# schematic-easyeda.net
KiCad netlist of a schematic drawn in EasyEDA
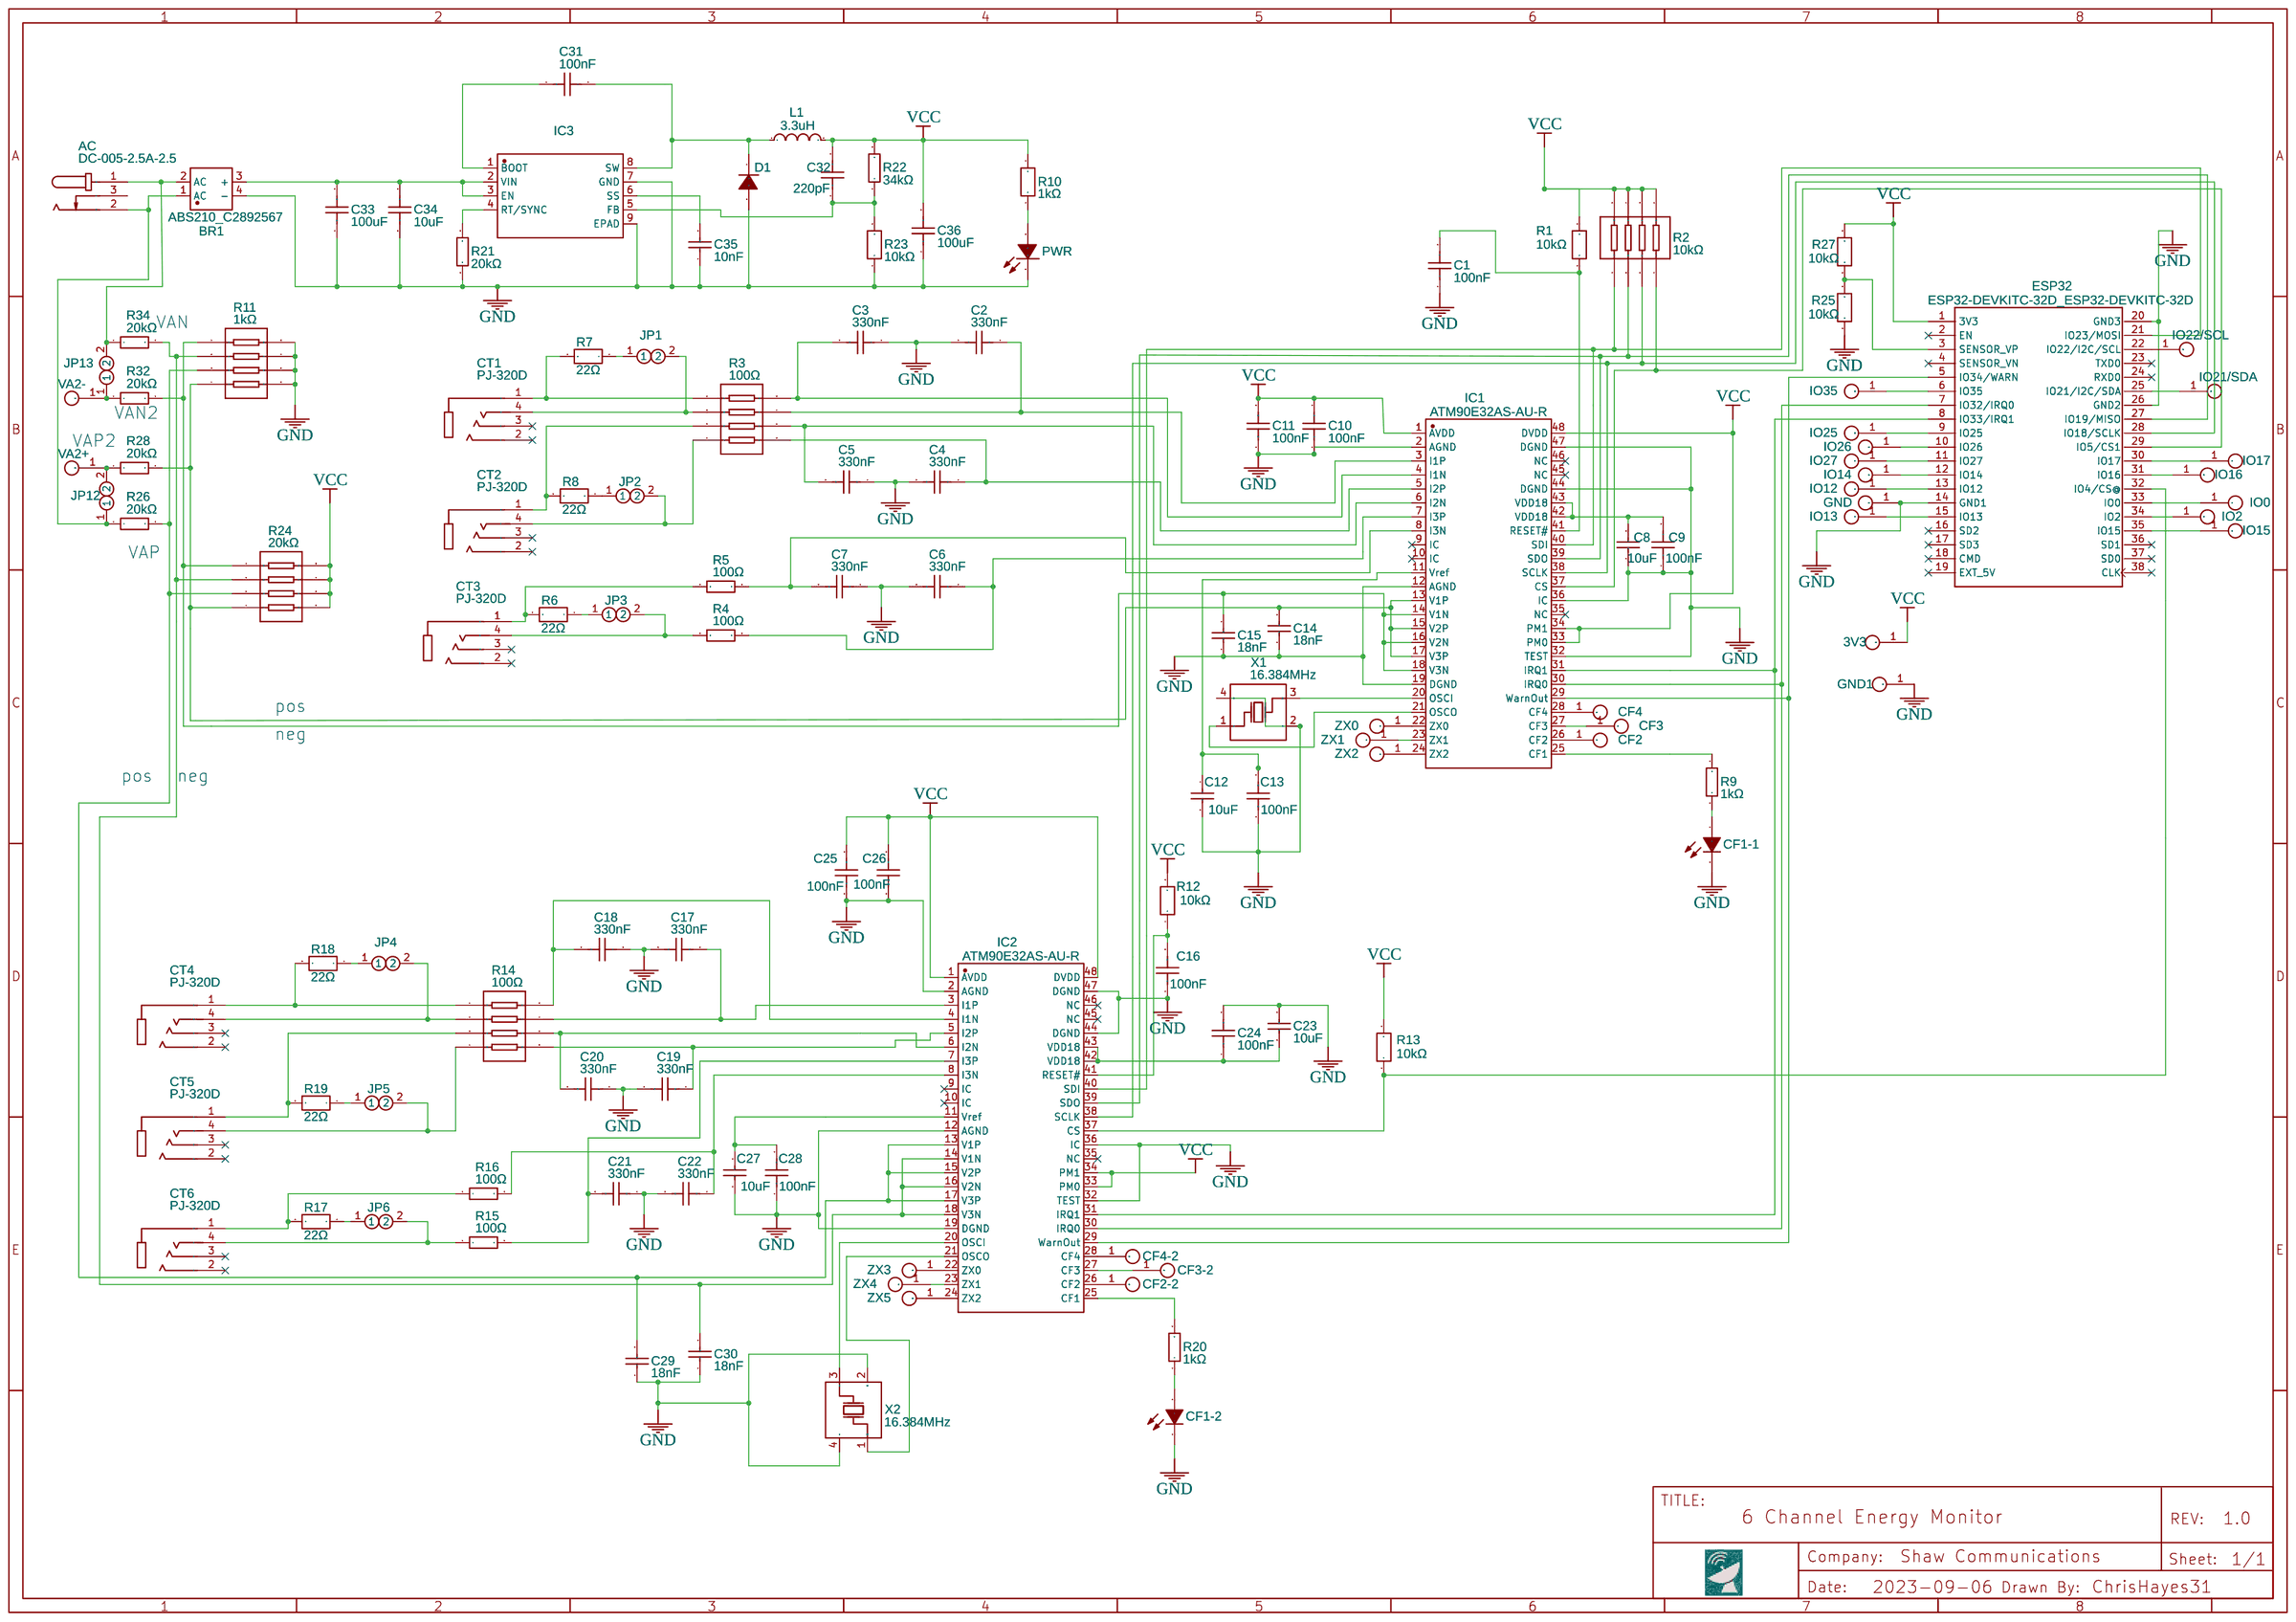
[diagram p0: schematic sheet]

(export (version "E")
  (design (tool "Eeschema 10.0.6"))
  (components
    (comp (ref "3V3") (value "PAD-ROUND") (libsource (lib "") (part "PAD-ROUND_5")))
    (comp (ref "AC")
      (value "DC-005-2.5A-2.5")
      (fields (field (name "Manufacturer") "XKB Enterprise"))
      (libsource (lib "") (part "DC-005-2.5A-2.5"))
    )
    (comp (ref "BR1")
      (value "ABS210_C2892567")
      (fields (field (name "Manufacturer Part") "ABS210") (field (name "Manufacturer") "YONGYUTAI(永裕泰)"))
      (libsource (lib "") (part "ABS210_C2892567"))
    )
    (comp (ref "C1")
      (value "100nF")
      (fields (field (name "Manufacturer Part") "CGJ4J2X7R1E104K125AA") (field (name "Manufacturer") "TDK"))
      (libsource (lib "") (part "CGJ4J2X7R1E104K125AA"))
    )
    (comp (ref "C2")
      (value "330nF")
      (fields
        (field (name "Manufacturer Part") "TCC0805X7R334K500DT")
        (field (name "Manufacturer") "CCTC(三环)")
      )
      (libsource (lib "") (part "TCC0805X7R334K500DT"))
    )
    (comp (ref "C3")
      (value "330nF")
      (fields
        (field (name "Manufacturer Part") "TCC0805X7R334K500DT")
        (field (name "Manufacturer") "CCTC(三环)")
      )
      (libsource (lib "") (part "TCC0805X7R334K500DT"))
    )
    (comp (ref "C4")
      (value "330nF")
      (fields
        (field (name "Manufacturer Part") "TCC0805X7R334K500DT")
        (field (name "Manufacturer") "CCTC(三环)")
      )
      (libsource (lib "") (part "TCC0805X7R334K500DT"))
    )
    (comp (ref "C5")
      (value "330nF")
      (fields
        (field (name "Manufacturer Part") "TCC0805X7R334K500DT")
        (field (name "Manufacturer") "CCTC(三环)")
      )
      (libsource (lib "") (part "TCC0805X7R334K500DT"))
    )
    (comp (ref "C6")
      (value "330nF")
      (fields
        (field (name "Manufacturer Part") "TCC0805X7R334K500DT")
        (field (name "Manufacturer") "CCTC(三环)")
      )
      (libsource (lib "") (part "TCC0805X7R334K500DT"))
    )
    (comp (ref "C7")
      (value "330nF")
      (fields
        (field (name "Manufacturer Part") "TCC0805X7R334K500DT")
        (field (name "Manufacturer") "CCTC(三环)")
      )
      (libsource (lib "") (part "TCC0805X7R334K500DT"))
    )
    (comp (ref "C8")
      (value "10uF")
      (fields
        (field (name "Manufacturer Part") "CC0805KKX5R8BB106")
        (field (name "Manufacturer") "YAGEO(国巨)")
      )
      (libsource (lib "") (part "CC0805KKX5R8BB106"))
    )
    (comp (ref "C9")
      (value "100nF")
      (fields (field (name "Manufacturer Part") "CGJ4J2X7R1E104K125AA") (field (name "Manufacturer") "TDK"))
      (libsource (lib "") (part "CGJ4J2X7R1E104K125AA"))
    )
    (comp (ref "C10")
      (value "100nF")
      (fields (field (name "Manufacturer Part") "CGJ4J2X7R1E104K125AA") (field (name "Manufacturer") "TDK"))
      (libsource (lib "") (part "CGJ4J2X7R1E104K125AA"))
    )
    (comp (ref "C11")
      (value "100nF")
      (fields (field (name "Manufacturer Part") "CGJ4J2X7R1E104K125AA") (field (name "Manufacturer") "TDK"))
      (libsource (lib "") (part "CGJ4J2X7R1E104K125AA"))
    )
    (comp (ref "C12")
      (value "10uF")
      (fields
        (field (name "Manufacturer Part") "CC0805KKX5R8BB106")
        (field (name "Manufacturer") "YAGEO(国巨)")
      )
      (libsource (lib "") (part "CC0805KKX5R8BB106_1"))
    )
    (comp (ref "C13")
      (value "100nF")
      (fields (field (name "Manufacturer Part") "CGJ4J2X7R1E104K125AA") (field (name "Manufacturer") "TDK"))
      (libsource (lib "") (part "CGJ4J2X7R1E104K125AA"))
    )
    (comp (ref "C14")
      (value "18nF")
      (fields
        (field (name "Manufacturer Part") "CC0805KRX7R9BB183")
        (field (name "Manufacturer") "YAGEO(国巨)")
      )
      (libsource (lib "") (part "CC0805KRX7R9BB183"))
    )
    (comp (ref "C15")
      (value "18nF")
      (fields
        (field (name "Manufacturer Part") "CC0805KRX7R9BB183")
        (field (name "Manufacturer") "YAGEO(国巨)")
      )
      (libsource (lib "") (part "CC0805KRX7R9BB183"))
    )
    (comp (ref "C16")
      (value "100nF")
      (fields (field (name "Manufacturer Part") "CGJ4J2X7R1E104K125AA") (field (name "Manufacturer") "TDK"))
      (libsource (lib "") (part "CGJ4J2X7R1E104K125AA"))
    )
    (comp (ref "C17")
      (value "330nF")
      (fields
        (field (name "Manufacturer Part") "TCC0805X7R334K500DT")
        (field (name "Manufacturer") "CCTC(三环)")
      )
      (libsource (lib "") (part "TCC0805X7R334K500DT"))
    )
    (comp (ref "C18")
      (value "330nF")
      (fields
        (field (name "Manufacturer Part") "TCC0805X7R334K500DT")
        (field (name "Manufacturer") "CCTC(三环)")
      )
      (libsource (lib "") (part "TCC0805X7R334K500DT"))
    )
    (comp (ref "C19")
      (value "330nF")
      (fields
        (field (name "Manufacturer Part") "TCC0805X7R334K500DT")
        (field (name "Manufacturer") "CCTC(三环)")
      )
      (libsource (lib "") (part "TCC0805X7R334K500DT"))
    )
    (comp (ref "C20")
      (value "330nF")
      (fields
        (field (name "Manufacturer Part") "TCC0805X7R334K500DT")
        (field (name "Manufacturer") "CCTC(三环)")
      )
      (libsource (lib "") (part "TCC0805X7R334K500DT"))
    )
    (comp (ref "C21")
      (value "330nF")
      (fields
        (field (name "Manufacturer Part") "TCC0805X7R334K500DT")
        (field (name "Manufacturer") "CCTC(三环)")
      )
      (libsource (lib "") (part "TCC0805X7R334K500DT"))
    )
    (comp (ref "C22")
      (value "330nF")
      (fields
        (field (name "Manufacturer Part") "TCC0805X7R334K500DT")
        (field (name "Manufacturer") "CCTC(三环)")
      )
      (libsource (lib "") (part "TCC0805X7R334K500DT"))
    )
    (comp (ref "C23")
      (value "10uF")
      (fields
        (field (name "Manufacturer Part") "CC0805KKX5R8BB106")
        (field (name "Manufacturer") "YAGEO(国巨)")
      )
      (libsource (lib "") (part "CC0805KKX5R8BB106"))
    )
    (comp (ref "C24")
      (value "100nF")
      (fields (field (name "Manufacturer Part") "CGJ4J2X7R1E104K125AA") (field (name "Manufacturer") "TDK"))
      (libsource (lib "") (part "CGJ4J2X7R1E104K125AA"))
    )
    (comp (ref "C25")
      (value "100nF")
      (fields (field (name "Manufacturer Part") "CGJ4J2X7R1E104K125AA") (field (name "Manufacturer") "TDK"))
      (libsource (lib "") (part "CGJ4J2X7R1E104K125AA"))
    )
    (comp (ref "C26")
      (value "100nF")
      (fields (field (name "Manufacturer Part") "CGJ4J2X7R1E104K125AA") (field (name "Manufacturer") "TDK"))
      (libsource (lib "") (part "CGJ4J2X7R1E104K125AA"))
    )
    (comp (ref "C27")
      (value "10uF")
      (fields
        (field (name "Manufacturer Part") "CC0805KKX5R8BB106")
        (field (name "Manufacturer") "YAGEO(国巨)")
      )
      (libsource (lib "") (part "CC0805KKX5R8BB106_1"))
    )
    (comp (ref "C28")
      (value "100nF")
      (fields (field (name "Manufacturer Part") "CGJ4J2X7R1E104K125AA") (field (name "Manufacturer") "TDK"))
      (libsource (lib "") (part "CGJ4J2X7R1E104K125AA"))
    )
    (comp (ref "C29")
      (value "18nF")
      (fields
        (field (name "Manufacturer Part") "CC0805KRX7R9BB183")
        (field (name "Manufacturer") "YAGEO(国巨)")
      )
      (libsource (lib "") (part "CC0805KRX7R9BB183"))
    )
    (comp (ref "C30")
      (value "18nF")
      (fields
        (field (name "Manufacturer Part") "CC0805KRX7R9BB183")
        (field (name "Manufacturer") "YAGEO(国巨)")
      )
      (libsource (lib "") (part "CC0805KRX7R9BB183"))
    )
    (comp (ref "C31")
      (value "100nF")
      (fields
        (field (name "Manufacturer Part") "CC0805JRX7R7BB104")
        (field (name "Manufacturer") "YAGEO(国巨)")
      )
      (libsource (lib "") (part "CC0805JRX7R7BB104"))
    )
    (comp (ref "C32")
      (value "220pF")
      (fields
        (field (name "Manufacturer Part") "CC0805JRNPO0BN221")
        (field (name "Manufacturer") "YAGEO(国巨)")
      )
      (libsource (lib "") (part "CC0805JRNPO0BN221"))
    )
    (comp (ref "C33")
      (value "100uF")
      (fields
        (field (name "Manufacturer Part") "GRM21BC80E107ME15L")
        (field (name "Manufacturer") "muRata(村田)")
      )
      (libsource (lib "") (part "GRM21BC80E107ME15L"))
    )
    (comp (ref "C34")
      (value "10uF")
      (fields
        (field (name "Manufacturer Part") "CC0805KKX7R7BB106")
        (field (name "Manufacturer") "YAGEO(国巨)")
      )
      (libsource (lib "") (part "CC0805KKX7R7BB106"))
    )
    (comp (ref "C35")
      (value "10nF")
      (fields
        (field (name "Manufacturer Part") "CC0805KKX7RBBB103")
        (field (name "Manufacturer") "YAGEO(国巨)")
      )
      (libsource (lib "") (part "CC0805KKX7RBBB103"))
    )
    (comp (ref "C36")
      (value "100uF")
      (fields
        (field (name "Manufacturer Part") "GRM21BC80E107ME15L")
        (field (name "Manufacturer") "muRata(村田)")
      )
      (libsource (lib "") (part "GRM21BC80E107ME15L"))
    )
    (comp (ref "CF1-1")
      (value "FC-DA1608BK-470H10")
      (fields (field (name "Manufacturer Part") "NCD0603B1") (field (name "Manufacturer") "国星光电"))
      (libsource (lib "") (part "FC-DA1608BK-470H10"))
    )
    (comp (ref "CF1-2")
      (value "FC-DA1608BK-470H10")
      (fields (field (name "Manufacturer Part") "NCD0603B1") (field (name "Manufacturer") "国星光电"))
      (libsource (lib "") (part "FC-DA1608BK-470H10"))
    )
    (comp (ref "CF2") (value "PAD-ROUND") (libsource (lib "") (part "PAD-ROUND_10")))
    (comp (ref "CF2-2") (value "PAD-ROUND") (libsource (lib "") (part "PAD-ROUND_2")))
    (comp (ref "CF3") (value "PAD-ROUND") (libsource (lib "") (part "PAD-ROUND_10")))
    (comp (ref "CF3-2") (value "PAD-ROUND") (libsource (lib "") (part "PAD-ROUND_12")))
    (comp (ref "CF4") (value "PAD-ROUND") (libsource (lib "") (part "PAD-ROUND_10")))
    (comp (ref "CF4-2") (value "PAD-ROUND") (libsource (lib "") (part "PAD-ROUND_9")))
    (comp (ref "CT1")
      (value "PJ-320D")
      (fields (field (name "Manufacturer") "SHOU HAN"))
      (libsource (lib "") (part "PJ-320D"))
    )
    (comp (ref "CT2")
      (value "PJ-320D")
      (fields (field (name "Manufacturer") "SHOU HAN"))
      (libsource (lib "") (part "PJ-320D"))
    )
    (comp (ref "CT3")
      (value "PJ-320D")
      (fields (field (name "Manufacturer") "SHOU HAN"))
      (libsource (lib "") (part "PJ-320D"))
    )
    (comp (ref "CT4")
      (value "PJ-320D")
      (fields (field (name "Manufacturer") "SHOU HAN"))
      (libsource (lib "") (part "PJ-320D"))
    )
    (comp (ref "CT5")
      (value "PJ-320D")
      (fields (field (name "Manufacturer") "SHOU HAN"))
      (libsource (lib "") (part "PJ-320D"))
    )
    (comp (ref "CT6")
      (value "PJ-320D")
      (fields (field (name "Manufacturer") "SHOU HAN"))
      (libsource (lib "") (part "PJ-320D"))
    )
    (comp (ref "D1")
      (value "M7_C95872")
      (fields (field (name "Manufacturer Part") "M7") (field (name "Manufacturer") "MDD"))
      (libsource (lib "") (part "M7_C95872"))
    )
    (comp (ref "ESP32")
      (value "ESP32-DEVKITC-32D_ESP32-DEVKITC-32D")
      (libsource (lib "") (part "ESP32-DEVKITC-32D_ESP32-DEVKITC-32D"))
    )
    (comp (ref "GND") (value "PAD-ROUND") (libsource (lib "") (part "PAD-ROUND_1")))
    (comp (ref "GND1") (value "PAD-ROUND") (libsource (lib "") (part "PAD-ROUND_1")))
    (comp (ref "IC1")
      (value "ATM90E32AS-AU-R")
      (fields (field (name "Manufacturer") "MICROCHIP(美国微芯)"))
      (libsource (lib "") (part "ATM90E32AS-AU-R"))
    )
    (comp (ref "IC2")
      (value "ATM90E32AS-AU-R")
      (fields (field (name "Manufacturer") "MICROCHIP(美国微芯)"))
      (libsource (lib "") (part "ATM90E32AS-AU-R"))
    )
    (comp (ref "IC3")
      (value "LMR14020SDDAR")
      (fields (field (name "Manufacturer") "TI(德州仪器)"))
      (libsource (lib "") (part "LMR14020SDDAR"))
    )
    (comp (ref "IO0") (value "PAD-ROUND") (libsource (lib "") (part "PAD-ROUND_3")))
    (comp (ref "IO2") (value "PAD-ROUND") (libsource (lib "") (part "PAD-ROUND_3")))
    (comp (ref "IO12") (value "PAD-ROUND") (libsource (lib "") (part "PAD-ROUND")))
    (comp (ref "IO13") (value "PAD-ROUND") (libsource (lib "") (part "PAD-ROUND")))
    (comp (ref "IO14") (value "PAD-ROUND") (libsource (lib "") (part "PAD-ROUND")))
    (comp (ref "IO15") (value "PAD-ROUND") (libsource (lib "") (part "PAD-ROUND_3")))
    (comp (ref "IO16") (value "PAD-ROUND") (libsource (lib "") (part "PAD-ROUND_3")))
    (comp (ref "IO17") (value "PAD-ROUND") (libsource (lib "") (part "PAD-ROUND_3")))
    (comp (ref "IO21/SDA") (value "PAD-ROUND") (libsource (lib "") (part "PAD-ROUND_8")))
    (comp (ref "IO22/SCL") (value "PAD-ROUND") (libsource (lib "") (part "PAD-ROUND_6")))
    (comp (ref "IO25") (value "PAD-ROUND") (libsource (lib "") (part "PAD-ROUND")))
    (comp (ref "IO26") (value "PAD-ROUND") (libsource (lib "") (part "PAD-ROUND")))
    (comp (ref "IO27") (value "PAD-ROUND") (libsource (lib "") (part "PAD-ROUND")))
    (comp (ref "IO35") (value "PAD-ROUND") (libsource (lib "") (part "PAD-ROUND")))
    (comp (ref "JP1") (value "J-pad soldering") (libsource (lib "") (part "J-pad soldering")))
    (comp (ref "JP2") (value "J-pad soldering") (libsource (lib "") (part "J-pad soldering")))
    (comp (ref "JP3") (value "J-pad soldering") (libsource (lib "") (part "J-pad soldering")))
    (comp (ref "JP4") (value "J-pad soldering") (libsource (lib "") (part "J-pad soldering")))
    (comp (ref "JP5") (value "J-pad soldering") (libsource (lib "") (part "J-pad soldering")))
    (comp (ref "JP6") (value "J-pad soldering") (libsource (lib "") (part "J-pad soldering")))
    (comp (ref "JP12") (value "J-pad soldering") (libsource (lib "") (part "J-pad soldering_1")))
    (comp (ref "JP13") (value "J-pad soldering") (libsource (lib "") (part "J-pad soldering_1")))
    (comp (ref "L1")
      (value "3.3uH")
      (fields (field (name "Manufacturer Part") "CYA0630-3.3UH") (field (name "Manufacturer") "SHOU HAN(首韩)"))
      (libsource (lib "") (part "CYA0630-3.3UH"))
    )
    (comp (ref "PWR")
      (value "EL0603/G6C-A01/DT(TS)(GW)")
      (fields (field (name "Manufacturer") "EVERLIGHT(亿光)"))
      (libsource (lib "") (part "EL0603/G6C-A01/DT(TS)(GW)"))
    )
    (comp (ref "R1")
      (value "10kΩ")
      (fields (field (name "Manufacturer Part") "SCR0805F10K") (field (name "Manufacturer") "VO(翔胜)"))
      (libsource (lib "") (part "SCR0805F10K"))
    )
    (comp (ref "R2")
      (value "10kΩ")
      (fields
        (field (name "Manufacturer Part") "4D03WGJ0103T5E")
        (field (name "Manufacturer") "UNI-ROYAL(厚声)")
      )
      (libsource (lib "") (part "4D03WGJ0103T5E"))
    )
    (comp (ref "R3")
      (value "100Ω")
      (fields
        (field (name "Manufacturer Part") "4D03WGJ0101T5E")
        (field (name "Manufacturer") "UNI-ROYAL(厚声)")
      )
      (libsource (lib "") (part "4D03WGJ0101T5E"))
    )
    (comp (ref "R4")
      (value "100Ω")
      (fields
        (field (name "Manufacturer Part") "0805W8F1000T5E")
        (field (name "Manufacturer") "UNI-ROYAL(厚声)")
      )
      (libsource (lib "") (part "0805W8F1000T5E"))
    )
    (comp (ref "R5")
      (value "100Ω")
      (fields
        (field (name "Manufacturer Part") "0805W8F1000T5E")
        (field (name "Manufacturer") "UNI-ROYAL(厚声)")
      )
      (libsource (lib "") (part "0805W8F1000T5E"))
    )
    (comp (ref "R6")
      (value "22Ω")
      (fields (field (name "Manufacturer Part") "SCR0805F22R") (field (name "Manufacturer") "VO(翔胜)"))
      (libsource (lib "") (part "SCR0805F22R"))
    )
    (comp (ref "R7")
      (value "22Ω")
      (fields (field (name "Manufacturer Part") "SCR0805F22R") (field (name "Manufacturer") "VO(翔胜)"))
      (libsource (lib "") (part "SCR0805F22R"))
    )
    (comp (ref "R8")
      (value "22Ω")
      (fields (field (name "Manufacturer Part") "SCR0805F22R") (field (name "Manufacturer") "VO(翔胜)"))
      (libsource (lib "") (part "SCR0805F22R"))
    )
    (comp (ref "R9")
      (value "1kΩ")
      (fields (field (name "Manufacturer Part") "CR0805F81001G") (field (name "Manufacturer") "LIZ(丽智电子)"))
      (libsource (lib "") (part "CR0805F81001G"))
    )
    (comp (ref "R10")
      (value "1kΩ")
      (fields (field (name "Manufacturer Part") "SCR0805F1K") (field (name "Manufacturer") "VO(翔胜)"))
      (libsource (lib "") (part "SCR0805F1K"))
    )
    (comp (ref "R11")
      (value "1kΩ")
      (fields
        (field (name "Manufacturer Part") "4D03WGJ0102T5E")
        (field (name "Manufacturer") "UNI-ROYAL(厚声)")
      )
      (libsource (lib "") (part "4D03WGJ0102T5E"))
    )
    (comp (ref "R12")
      (value "10kΩ")
      (fields (field (name "Manufacturer Part") "SCR0805F10K") (field (name "Manufacturer") "VO(翔胜)"))
      (libsource (lib "") (part "SCR0805F10K"))
    )
    (comp (ref "R13")
      (value "10kΩ")
      (fields (field (name "Manufacturer Part") "SCR0805F10K") (field (name "Manufacturer") "VO(翔胜)"))
      (libsource (lib "") (part "SCR0805F10K"))
    )
    (comp (ref "R14")
      (value "100Ω")
      (fields
        (field (name "Manufacturer Part") "4D03WGJ0101T5E")
        (field (name "Manufacturer") "UNI-ROYAL(厚声)")
      )
      (libsource (lib "") (part "4D03WGJ0101T5E"))
    )
    (comp (ref "R15")
      (value "100Ω")
      (fields
        (field (name "Manufacturer Part") "0805W8F1000T5E")
        (field (name "Manufacturer") "UNI-ROYAL(厚声)")
      )
      (libsource (lib "") (part "0805W8F1000T5E"))
    )
    (comp (ref "R16")
      (value "100Ω")
      (fields
        (field (name "Manufacturer Part") "0805W8F1000T5E")
        (field (name "Manufacturer") "UNI-ROYAL(厚声)")
      )
      (libsource (lib "") (part "0805W8F1000T5E"))
    )
    (comp (ref "R17")
      (value "22Ω")
      (fields (field (name "Manufacturer Part") "SCR0805F22R") (field (name "Manufacturer") "VO(翔胜)"))
      (libsource (lib "") (part "SCR0805F22R"))
    )
    (comp (ref "R18")
      (value "22Ω")
      (fields (field (name "Manufacturer Part") "SCR0805F22R") (field (name "Manufacturer") "VO(翔胜)"))
      (libsource (lib "") (part "SCR0805F22R"))
    )
    (comp (ref "R19")
      (value "22Ω")
      (fields (field (name "Manufacturer Part") "SCR0805F22R") (field (name "Manufacturer") "VO(翔胜)"))
      (libsource (lib "") (part "SCR0805F22R"))
    )
    (comp (ref "R20")
      (value "1kΩ")
      (fields (field (name "Manufacturer Part") "CR0805F81001G") (field (name "Manufacturer") "LIZ(丽智电子)"))
      (libsource (lib "") (part "CR0805F81001G"))
    )
    (comp (ref "R21")
      (value "20kΩ")
      (fields
        (field (name "Manufacturer Part") "QR0805F20K0P05Z")
        (field (name "Manufacturer") "EVER OHMS(天二科技)")
      )
      (libsource (lib "") (part "QR0805F20KP05"))
    )
    (comp (ref "R22")
      (value "34kΩ")
      (fields (field (name "Manufacturer Part") "AC0805FR-0734KL") (field (name "Manufacturer") "YAGEO(国巨)"))
      (libsource (lib "") (part "AC0805FR-0734KL"))
    )
    (comp (ref "R23")
      (value "10kΩ")
      (fields
        (field (name "Manufacturer Part") "CR0805J10K0P05Z")
        (field (name "Manufacturer") "EVER OHMS(天二科技)")
      )
      (libsource (lib "") (part "CR0805J10K0P05Z"))
    )
    (comp (ref "R24")
      (value "20kΩ")
      (fields
        (field (name "Manufacturer Part") "4D03WGJ0203T5E")
        (field (name "Manufacturer") "UNI-ROYAL(厚声)")
      )
      (libsource (lib "") (part "4D03WGJ0203T5E"))
    )
    (comp (ref "R25")
      (value "10kΩ")
      (fields (field (name "Manufacturer Part") "SCR0805F10K") (field (name "Manufacturer") "VO(翔胜)"))
      (libsource (lib "") (part "SCR0805F10K"))
    )
    (comp (ref "R26")
      (value "20kΩ")
      (fields (field (name "Manufacturer Part") "RK73H2ATTD2002F") (field (name "Manufacturer") "KOA"))
      (libsource (lib "") (part "RK73H2ATTD2002F"))
    )
    (comp (ref "R27")
      (value "10kΩ")
      (fields (field (name "Manufacturer Part") "SCR0805F10K") (field (name "Manufacturer") "VO(翔胜)"))
      (libsource (lib "") (part "SCR0805F10K"))
    )
    (comp (ref "R28")
      (value "20kΩ")
      (fields (field (name "Manufacturer Part") "RK73H2ATTD2002F") (field (name "Manufacturer") "KOA"))
      (libsource (lib "") (part "RK73H2ATTD2002F"))
    )
    (comp (ref "R32")
      (value "20kΩ")
      (fields (field (name "Manufacturer Part") "RK73H2ATTD2002F") (field (name "Manufacturer") "KOA"))
      (libsource (lib "") (part "RK73H2ATTD2002F"))
    )
    (comp (ref "R34")
      (value "20kΩ")
      (fields (field (name "Manufacturer Part") "RK73H2ATTD2002F") (field (name "Manufacturer") "KOA"))
      (libsource (lib "") (part "RK73H2ATTD2002F"))
    )
    (comp (ref "VA2+") (value "PAD-ROUND") (libsource (lib "") (part "PAD-ROUND_11")))
    (comp (ref "VA2-") (value "PAD-ROUND") (libsource (lib "") (part "PAD-ROUND_7")))
    (comp (ref "X1")
      (value "16.384MHz")
      (fields (field (name "Manufacturer Part") "X322516384MSB4SI") (field (name "Manufacturer") "YXC(扬兴晶振)"))
      (libsource (lib "") (part "X322516384MSB4SI"))
    )
    (comp (ref "X2")
      (value "16.384MHz")
      (fields (field (name "Manufacturer Part") "X322516384MSB4SI") (field (name "Manufacturer") "YXC(扬兴晶振)"))
      (libsource (lib "") (part "X322516384MSB4SI_1"))
    )
    (comp (ref "ZX0") (value "PAD-ROUND") (libsource (lib "") (part "PAD-ROUND_4")))
    (comp (ref "ZX1") (value "PAD-ROUND") (libsource (lib "") (part "PAD-ROUND_4")))
    (comp (ref "ZX2") (value "PAD-ROUND") (libsource (lib "") (part "PAD-ROUND_4")))
    (comp (ref "ZX3") (value "PAD-ROUND") (libsource (lib "") (part "PAD-ROUND_4")))
    (comp (ref "ZX4") (value "PAD-ROUND") (libsource (lib "") (part "PAD-ROUND_4")))
    (comp (ref "ZX5") (value "PAD-ROUND") (libsource (lib "") (part "PAD-ROUND_4")))
  )
  (nets
    (net (code "1") (name "GND") (class "Default")
      (node (ref "BR1") (pin "4") (pinfunction "-_4") (pintype "unspecified"))
      (node (ref "C1") (pin "1") (pinfunction "1_1") (pintype "unspecified"))
      (node (ref "C10") (pin "1") (pinfunction "1_1") (pintype "unspecified"))
      (node (ref "C11") (pin "1") (pinfunction "1_1") (pintype "unspecified"))
      (node (ref "C12") (pin "2") (pinfunction "2_2") (pintype "input"))
      (node (ref "C13") (pin "1") (pinfunction "1_1") (pintype "unspecified"))
      (node (ref "C14") (pin "1") (pinfunction "1_1") (pintype "input"))
      (node (ref "C15") (pin "1") (pinfunction "1_1") (pintype "input"))
      (node (ref "C16") (pin "1") (pinfunction "1_1") (pintype "unspecified"))
      (node (ref "C17") (pin "2") (pinfunction "2_2") (pintype "unspecified"))
      (node (ref "C18") (pin "1") (pinfunction "1_1") (pintype "unspecified"))
      (node (ref "C19") (pin "2") (pinfunction "2_2") (pintype "unspecified"))
      (node (ref "C2") (pin "2") (pinfunction "2_2") (pintype "unspecified"))
      (node (ref "C20") (pin "1") (pinfunction "1_1") (pintype "unspecified"))
      (node (ref "C21") (pin "1") (pinfunction "1_1") (pintype "unspecified"))
      (node (ref "C22") (pin "2") (pinfunction "2_2") (pintype "unspecified"))
      (node (ref "C23") (pin "2") (pinfunction "2_2") (pintype "input"))
      (node (ref "C24") (pin "2") (pinfunction "2_2") (pintype "unspecified"))
      (node (ref "C25") (pin "1") (pinfunction "1_1") (pintype "unspecified"))
      (node (ref "C26") (pin "1") (pinfunction "1_1") (pintype "unspecified"))
      (node (ref "C27") (pin "2") (pinfunction "2_2") (pintype "input"))
      (node (ref "C28") (pin "1") (pinfunction "1_1") (pintype "unspecified"))
      (node (ref "C29") (pin "1") (pinfunction "1_1") (pintype "input"))
      (node (ref "C3") (pin "1") (pinfunction "1_1") (pintype "unspecified"))
      (node (ref "C30") (pin "1") (pinfunction "1_1") (pintype "input"))
      (node (ref "C33") (pin "1") (pinfunction "1_1") (pintype "unspecified"))
      (node (ref "C34") (pin "2") (pinfunction "2_2") (pintype "unspecified"))
      (node (ref "C35") (pin "1") (pinfunction "1_1") (pintype "input"))
      (node (ref "C36") (pin "1") (pinfunction "1_1") (pintype "unspecified"))
      (node (ref "C4") (pin "2") (pinfunction "2_2") (pintype "unspecified"))
      (node (ref "C5") (pin "1") (pinfunction "1_1") (pintype "unspecified"))
      (node (ref "C6") (pin "2") (pinfunction "2_2") (pintype "unspecified"))
      (node (ref "C7") (pin "1") (pinfunction "1_1") (pintype "unspecified"))
      (node (ref "C8") (pin "1") (pinfunction "1_1") (pintype "input"))
      (node (ref "C9") (pin "1") (pinfunction "1_1") (pintype "unspecified"))
      (node (ref "CF1-1") (pin "1") (pinfunction "-_1") (pintype "input"))
      (node (ref "CF1-2") (pin "1") (pinfunction "-_1") (pintype "input"))
      (node (ref "D1") (pin "2") (pinfunction "A_2") (pintype "unspecified"))
      (node (ref "ESP32") (pin "14") (pinfunction "GND1_14") (pintype "bidirectional"))
      (node (ref "ESP32") (pin "20") (pinfunction "GND3_20") (pintype "bidirectional"))
      (node (ref "ESP32") (pin "26") (pinfunction "GND2_26") (pintype "bidirectional"))
      (node (ref "GND") (pin "1") (pinfunction "Pad_1") (pintype "unspecified"))
      (node (ref "GND1") (pin "1") (pinfunction "Pad_1") (pintype "unspecified"))
      (node (ref "IC1") (pin "12") (pinfunction "AGND_12") (pintype "unspecified"))
      (node (ref "IC1") (pin "19") (pinfunction "DGND_19") (pintype "unspecified"))
      (node (ref "IC1") (pin "2") (pinfunction "AGND_2") (pintype "unspecified"))
      (node (ref "IC1") (pin "32") (pinfunction "TEST_32") (pintype "unspecified"))
      (node (ref "IC1") (pin "36") (pinfunction "IC_36") (pintype "unspecified"))
      (node (ref "IC1") (pin "44") (pinfunction "DGND_44") (pintype "unspecified"))
      (node (ref "IC1") (pin "47") (pinfunction "DGND_47") (pintype "unspecified"))
      (node (ref "IC2") (pin "12") (pinfunction "AGND_12") (pintype "unspecified"))
      (node (ref "IC2") (pin "19") (pinfunction "DGND_19") (pintype "unspecified"))
      (node (ref "IC2") (pin "2") (pinfunction "AGND_2") (pintype "unspecified"))
      (node (ref "IC2") (pin "32") (pinfunction "TEST_32") (pintype "unspecified"))
      (node (ref "IC2") (pin "36") (pinfunction "IC_36") (pintype "unspecified"))
      (node (ref "IC2") (pin "44") (pinfunction "DGND_44") (pintype "unspecified"))
      (node (ref "IC2") (pin "47") (pinfunction "DGND_47") (pintype "unspecified"))
      (node (ref "IC3") (pin "7") (pinfunction "GND_7") (pintype "unspecified"))
      (node (ref "IC3") (pin "9") (pinfunction "EPAD_9") (pintype "unspecified"))
      (node (ref "PWR") (pin "2") (pinfunction "K_2") (pintype "unspecified"))
      (node (ref "R11") (pin "5") (pinfunction "5_5") (pintype "input"))
      (node (ref "R11") (pin "6") (pinfunction "6_6") (pintype "input"))
      (node (ref "R11") (pin "7") (pinfunction "7_7") (pintype "input"))
      (node (ref "R11") (pin "8") (pinfunction "8_8") (pintype "input"))
      (node (ref "R21") (pin "1") (pinfunction "1_1") (pintype "unspecified"))
      (node (ref "R23") (pin "1") (pinfunction "1_1") (pintype "unspecified"))
      (node (ref "R25") (pin "1") (pinfunction "1_1") (pintype "unspecified"))
      (node (ref "X1") (pin "2") (pinfunction "GND_2") (pintype "unspecified"))
      (node (ref "X1") (pin "4") (pinfunction "GND_4") (pintype "unspecified"))
      (node (ref "X2") (pin "2") (pinfunction "GND_2") (pintype "unspecified"))
      (node (ref "X2") (pin "4") (pinfunction "GND_4") (pintype "unspecified"))
    )
    (net (code "2") (name "Net-(AC-Pad1)") (class "Default")
      (node (ref "AC") (pin "1") (pinfunction "1_1") (pintype "unspecified"))
      (node (ref "BR1") (pin "2") (pinfunction "AC_2") (pintype "unspecified"))
      (node (ref "JP13") (pin "2") (pinfunction "2_2") (pintype "unspecified"))
      (node (ref "R34") (pin "1") (pinfunction "1_1") (pintype "unspecified"))
    )
    (net (code "3") (name "Net-(AC-Pad2)") (class "Default")
      (node (ref "AC") (pin "2") (pinfunction "2_2") (pintype "unspecified"))
      (node (ref "BR1") (pin "1") (pinfunction "AC_1") (pintype "unspecified"))
      (node (ref "JP12") (pin "1") (pinfunction "1_1") (pintype "unspecified"))
      (node (ref "R26") (pin "1") (pinfunction "1_1") (pintype "unspecified"))
    )
    (net (code "4") (name "Net-(BR1-+)") (class "Default")
      (node (ref "BR1") (pin "3") (pinfunction "+_3") (pintype "unspecified"))
      (node (ref "C33") (pin "2") (pinfunction "2_2") (pintype "unspecified"))
      (node (ref "C34") (pin "1") (pinfunction "1_1") (pintype "unspecified"))
      (node (ref "IC3") (pin "2") (pinfunction "VIN_2") (pintype "unspecified"))
      (node (ref "IC3") (pin "3") (pinfunction "EN_3") (pintype "unspecified"))
    )
    (net (code "5") (name "Net-(C8-Pad2)") (class "Default")
      (node (ref "C8") (pin "2") (pinfunction "2_2") (pintype "input"))
      (node (ref "C9") (pin "2") (pinfunction "2_2") (pintype "unspecified"))
      (node (ref "IC1") (pin "42") (pinfunction "VDD18_42") (pintype "unspecified"))
      (node (ref "IC1") (pin "43") (pinfunction "VDD18_43") (pintype "unspecified"))
    )
    (net (code "6") (name "Net-(C23-Pad1)") (class "Default")
      (node (ref "C23") (pin "1") (pinfunction "1_1") (pintype "input"))
      (node (ref "C24") (pin "1") (pinfunction "1_1") (pintype "unspecified"))
      (node (ref "IC2") (pin "42") (pinfunction "VDD18_42") (pintype "unspecified"))
      (node (ref "IC2") (pin "43") (pinfunction "VDD18_43") (pintype "unspecified"))
    )
    (net (code "7") (name "Net-(CF1-1-+)") (class "Default")
      (node (ref "CF1-1") (pin "2") (pinfunction "+_2") (pintype "input"))
      (node (ref "R9") (pin "1") (pinfunction "1_1") (pintype "input"))
    )
    (net (code "8") (name "Net-(CF1-2-+)") (class "Default")
      (node (ref "CF1-2") (pin "2") (pinfunction "+_2") (pintype "input"))
      (node (ref "R20") (pin "1") (pinfunction "1_1") (pintype "input"))
    )
    (net (code "9") (name "Net-(CT1-Pad1)") (class "Default")
      (node (ref "CT1") (pin "1") (pinfunction "1_1") (pintype "unspecified"))
      (node (ref "R3") (pin "1") (pinfunction "1_1") (pintype "input"))
      (node (ref "R7") (pin "2") (pinfunction "2_2") (pintype "unspecified"))
    )
    (net (code "10") (name "Net-(CT1-Pad4)") (class "Default")
      (node (ref "CT1") (pin "4") (pinfunction "4_4") (pintype "unspecified"))
      (node (ref "JP1") (pin "2") (pinfunction "2_2") (pintype "unspecified"))
      (node (ref "R3") (pin "2") (pinfunction "2_2") (pintype "input"))
    )
    (net (code "11") (name "Net-(CT2-Pad1)") (class "Default")
      (node (ref "CT2") (pin "1") (pinfunction "1_1") (pintype "unspecified"))
      (node (ref "R3") (pin "3") (pinfunction "3_3") (pintype "input"))
      (node (ref "R8") (pin "2") (pinfunction "2_2") (pintype "unspecified"))
    )
    (net (code "12") (name "Net-(CT2-Pad4)") (class "Default")
      (node (ref "CT2") (pin "4") (pinfunction "4_4") (pintype "unspecified"))
      (node (ref "JP2") (pin "2") (pinfunction "2_2") (pintype "unspecified"))
      (node (ref "R3") (pin "4") (pinfunction "4_4") (pintype "input"))
    )
    (net (code "13") (name "Net-(CT3-Pad1)") (class "Default")
      (node (ref "CT3") (pin "1") (pinfunction "1_1") (pintype "unspecified"))
      (node (ref "R5") (pin "1") (pinfunction "1_1") (pintype "input"))
      (node (ref "R6") (pin "2") (pinfunction "2_2") (pintype "unspecified"))
    )
    (net (code "14") (name "Net-(CT3-Pad4)") (class "Default")
      (node (ref "CT3") (pin "4") (pinfunction "4_4") (pintype "unspecified"))
      (node (ref "JP3") (pin "2") (pinfunction "2_2") (pintype "unspecified"))
      (node (ref "R4") (pin "1") (pinfunction "1_1") (pintype "input"))
    )
    (net (code "15") (name "Net-(CT4-Pad1)") (class "Default")
      (node (ref "CT4") (pin "1") (pinfunction "1_1") (pintype "unspecified"))
      (node (ref "R14") (pin "1") (pinfunction "1_1") (pintype "input"))
      (node (ref "R18") (pin "2") (pinfunction "2_2") (pintype "unspecified"))
    )
    (net (code "16") (name "Net-(CT4-Pad4)") (class "Default")
      (node (ref "CT4") (pin "4") (pinfunction "4_4") (pintype "unspecified"))
      (node (ref "JP4") (pin "2") (pinfunction "2_2") (pintype "unspecified"))
      (node (ref "R14") (pin "2") (pinfunction "2_2") (pintype "input"))
    )
    (net (code "17") (name "Net-(CT5-Pad1)") (class "Default")
      (node (ref "CT5") (pin "1") (pinfunction "1_1") (pintype "unspecified"))
      (node (ref "R14") (pin "3") (pinfunction "3_3") (pintype "input"))
      (node (ref "R19") (pin "2") (pinfunction "2_2") (pintype "unspecified"))
    )
    (net (code "18") (name "Net-(CT5-Pad4)") (class "Default")
      (node (ref "CT5") (pin "4") (pinfunction "4_4") (pintype "unspecified"))
      (node (ref "JP5") (pin "2") (pinfunction "2_2") (pintype "unspecified"))
      (node (ref "R14") (pin "4") (pinfunction "4_4") (pintype "input"))
    )
    (net (code "19") (name "Net-(CT6-Pad1)") (class "Default")
      (node (ref "CT6") (pin "1") (pinfunction "1_1") (pintype "unspecified"))
      (node (ref "R16") (pin "1") (pinfunction "1_1") (pintype "input"))
      (node (ref "R17") (pin "2") (pinfunction "2_2") (pintype "unspecified"))
    )
    (net (code "20") (name "Net-(CT6-Pad4)") (class "Default")
      (node (ref "CT6") (pin "4") (pinfunction "4_4") (pintype "unspecified"))
      (node (ref "JP6") (pin "2") (pinfunction "2_2") (pintype "unspecified"))
      (node (ref "R15") (pin "1") (pinfunction "1_1") (pintype "input"))
    )
    (net (code "21") (name "Net-(D1-K)") (class "Default")
      (node (ref "C31") (pin "1") (pinfunction "1_1") (pintype "unspecified"))
      (node (ref "D1") (pin "1") (pinfunction "K_1") (pintype "unspecified"))
      (node (ref "IC3") (pin "8") (pinfunction "SW_8") (pintype "unspecified"))
      (node (ref "L1") (pin "1") (pinfunction "1_1") (pintype "unspecified"))
    )
    (net (code "22") (name "Net-(ESP32-IO0)") (class "Default")
      (node (ref "ESP32") (pin "33") (pinfunction "IO0_33") (pintype "bidirectional"))
      (node (ref "IO0") (pin "1") (pinfunction "Pad_1") (pintype "unspecified"))
    )
    (net (code "23") (name "Net-(ESP32-IO2)") (class "Default")
      (node (ref "ESP32") (pin "34") (pinfunction "IO2_34") (pintype "bidirectional"))
      (node (ref "IO2") (pin "1") (pinfunction "Pad_1") (pintype "unspecified"))
    )
    (net (code "24") (name "Net-(ESP32-IO4{slash}CS@)") (class "Default")
      (node (ref "ESP32") (pin "32") (pinfunction "IO4/CS@_32") (pintype "bidirectional"))
      (node (ref "IC2") (pin "37") (pinfunction "CS_37") (pintype "unspecified"))
      (node (ref "R13") (pin "1") (pinfunction "1_1") (pintype "unspecified"))
    )
    (net (code "25") (name "Net-(ESP32-IO5{slash}CS1)") (class "Default")
      (node (ref "ESP32") (pin "29") (pinfunction "IO5/CS1_29") (pintype "bidirectional"))
      (node (ref "IC1") (pin "37") (pinfunction "CS_37") (pintype "unspecified"))
      (node (ref "R2") (pin "4") (pinfunction "4_4") (pintype "input"))
    )
    (net (code "26") (name "Net-(ESP32-IO12)") (class "Default")
      (node (ref "ESP32") (pin "13") (pinfunction "IO12_13") (pintype "bidirectional"))
      (node (ref "IO12") (pin "1") (pinfunction "Pad_1") (pintype "unspecified"))
    )
    (net (code "27") (name "Net-(ESP32-IO13)") (class "Default")
      (node (ref "ESP32") (pin "15") (pinfunction "IO13_15") (pintype "bidirectional"))
      (node (ref "IO13") (pin "1") (pinfunction "Pad_1") (pintype "unspecified"))
    )
    (net (code "28") (name "Net-(ESP32-IO14)") (class "Default")
      (node (ref "ESP32") (pin "12") (pinfunction "IO14_12") (pintype "bidirectional"))
      (node (ref "IO14") (pin "1") (pinfunction "Pad_1") (pintype "unspecified"))
    )
    (net (code "29") (name "Net-(ESP32-IO15)") (class "Default")
      (node (ref "ESP32") (pin "35") (pinfunction "IO15_35") (pintype "bidirectional"))
      (node (ref "IO15") (pin "1") (pinfunction "Pad_1") (pintype "unspecified"))
    )
    (net (code "30") (name "Net-(ESP32-IO16)") (class "Default")
      (node (ref "ESP32") (pin "31") (pinfunction "IO16_31") (pintype "bidirectional"))
      (node (ref "IO16") (pin "1") (pinfunction "Pad_1") (pintype "unspecified"))
    )
    (net (code "31") (name "Net-(ESP32-IO17)") (class "Default")
      (node (ref "ESP32") (pin "30") (pinfunction "IO17_30") (pintype "bidirectional"))
      (node (ref "IO17") (pin "1") (pinfunction "Pad_1") (pintype "unspecified"))
    )
    (net (code "32") (name "Net-(ESP32-IO18{slash}SCLK)") (class "Default")
      (node (ref "ESP32") (pin "28") (pinfunction "IO18/SCLK_28") (pintype "bidirectional"))
      (node (ref "IC1") (pin "38") (pinfunction "SCLK_38") (pintype "unspecified"))
      (node (ref "IC2") (pin "38") (pinfunction "SCLK_38") (pintype "unspecified"))
      (node (ref "R2") (pin "3") (pinfunction "3_3") (pintype "input"))
    )
    (net (code "33") (name "Net-(ESP32-IO19{slash}MISO)") (class "Default")
      (node (ref "ESP32") (pin "27") (pinfunction "IO19/MISO_27") (pintype "bidirectional"))
      (node (ref "IC1") (pin "39") (pinfunction "SDO_39") (pintype "unspecified"))
      (node (ref "IC2") (pin "39") (pinfunction "SDO_39") (pintype "unspecified"))
      (node (ref "R2") (pin "2") (pinfunction "2_2") (pintype "input"))
    )
    (net (code "34") (name "Net-(ESP32-IO21{slash}I2C{slash}SDA)") (class "Default")
      (node (ref "ESP32") (pin "25") (pinfunction "IO21/I2C/SDA_25") (pintype "bidirectional"))
      (node (ref "IO21/SDA") (pin "1") (pinfunction "Pad_1") (pintype "unspecified"))
    )
    (net (code "35") (name "Net-(ESP32-IO22{slash}I2C{slash}SCL)") (class "Default")
      (node (ref "ESP32") (pin "22") (pinfunction "IO22/I2C/SCL_22") (pintype "bidirectional"))
      (node (ref "IO22/SCL") (pin "1") (pinfunction "Pad_1") (pintype "unspecified"))
    )
    (net (code "36") (name "Net-(ESP32-IO23{slash}MOSI)") (class "Default")
      (node (ref "ESP32") (pin "21") (pinfunction "IO23/MOSI_21") (pintype "bidirectional"))
      (node (ref "IC1") (pin "40") (pinfunction "SDI_40") (pintype "unspecified"))
      (node (ref "IC2") (pin "40") (pinfunction "SDI_40") (pintype "unspecified"))
      (node (ref "R2") (pin "1") (pinfunction "1_1") (pintype "input"))
    )
    (net (code "37") (name "Net-(ESP32-IO25)") (class "Default")
      (node (ref "ESP32") (pin "9") (pinfunction "IO25_9") (pintype "bidirectional"))
      (node (ref "IO25") (pin "1") (pinfunction "Pad_1") (pintype "unspecified"))
    )
    (net (code "38") (name "Net-(ESP32-IO26)") (class "Default")
      (node (ref "ESP32") (pin "10") (pinfunction "IO26_10") (pintype "bidirectional"))
      (node (ref "IO26") (pin "1") (pinfunction "Pad_1") (pintype "unspecified"))
    )
    (net (code "39") (name "Net-(ESP32-IO27)") (class "Default")
      (node (ref "ESP32") (pin "11") (pinfunction "IO27_11") (pintype "bidirectional"))
      (node (ref "IO27") (pin "1") (pinfunction "Pad_1") (pintype "unspecified"))
    )
    (net (code "40") (name "Net-(ESP32-IO32{slash}IRQ0)") (class "Default")
      (node (ref "ESP32") (pin "7") (pinfunction "IO32/IRQ0_7") (pintype "bidirectional"))
      (node (ref "IC1") (pin "30") (pinfunction "IRQ0_30") (pintype "unspecified"))
      (node (ref "IC2") (pin "30") (pinfunction "IRQ0_30") (pintype "unspecified"))
    )
    (net (code "41") (name "Net-(ESP32-IO33{slash}IRQ1)") (class "Default")
      (node (ref "ESP32") (pin "8") (pinfunction "IO33/IRQ1_8") (pintype "bidirectional"))
      (node (ref "IC1") (pin "31") (pinfunction "IRQ1_31") (pintype "unspecified"))
      (node (ref "IC2") (pin "31") (pinfunction "IRQ1_31") (pintype "unspecified"))
    )
    (net (code "42") (name "Net-(ESP32-IO34{slash}WARN)") (class "Default")
      (node (ref "ESP32") (pin "5") (pinfunction "IO34/WARN_5") (pintype "bidirectional"))
      (node (ref "IC1") (pin "29") (pinfunction "WarnOut_29") (pintype "unspecified"))
      (node (ref "IC2") (pin "29") (pinfunction "WarnOut_29") (pintype "unspecified"))
    )
    (net (code "43") (name "Net-(ESP32-IO35)") (class "Default")
      (node (ref "ESP32") (pin "6") (pinfunction "IO35_6") (pintype "bidirectional"))
      (node (ref "IO35") (pin "1") (pinfunction "Pad_1") (pintype "unspecified"))
    )
    (net (code "44") (name "Net-(ESP32-SENSOR_VP)") (class "Default")
      (node (ref "ESP32") (pin "3") (pinfunction "SENSOR_VP_3") (pintype "bidirectional"))
      (node (ref "R25") (pin "2") (pinfunction "2_2") (pintype "unspecified"))
      (node (ref "R27") (pin "1") (pinfunction "1_1") (pintype "unspecified"))
    )
    (net (code "45") (name "Net-(IC1-CF1)") (class "Default")
      (node (ref "IC1") (pin "25") (pinfunction "CF1_25") (pintype "unspecified"))
      (node (ref "R9") (pin "2") (pinfunction "2_2") (pintype "input"))
    )
    (net (code "46") (name "Net-(IC1-CF2)") (class "Default")
      (node (ref "CF2") (pin "1") (pinfunction "Pad_1") (pintype "unspecified"))
      (node (ref "IC1") (pin "26") (pinfunction "CF2_26") (pintype "unspecified"))
    )
    (net (code "47") (name "Net-(IC1-CF3)") (class "Default")
      (node (ref "CF3") (pin "1") (pinfunction "Pad_1") (pintype "unspecified"))
      (node (ref "IC1") (pin "27") (pinfunction "CF3_27") (pintype "unspecified"))
    )
    (net (code "48") (name "Net-(IC1-CF4)") (class "Default")
      (node (ref "CF4") (pin "1") (pinfunction "Pad_1") (pintype "unspecified"))
      (node (ref "IC1") (pin "28") (pinfunction "CF4_28") (pintype "unspecified"))
    )
    (net (code "49") (name "Net-(IC1-I1N)") (class "Default")
      (node (ref "C3") (pin "2") (pinfunction "2_2") (pintype "unspecified"))
      (node (ref "IC1") (pin "4") (pinfunction "I1N_4") (pintype "unspecified"))
      (node (ref "R3") (pin "8") (pinfunction "8_8") (pintype "input"))
    )
    (net (code "50") (name "Net-(IC1-I1P)") (class "Default")
      (node (ref "C2") (pin "1") (pinfunction "1_1") (pintype "unspecified"))
      (node (ref "IC1") (pin "3") (pinfunction "I1P_3") (pintype "unspecified"))
      (node (ref "R3") (pin "7") (pinfunction "7_7") (pintype "input"))
    )
    (net (code "51") (name "Net-(IC1-I2N)") (class "Default")
      (node (ref "C5") (pin "2") (pinfunction "2_2") (pintype "unspecified"))
      (node (ref "IC1") (pin "6") (pinfunction "I2N_6") (pintype "unspecified"))
      (node (ref "R3") (pin "6") (pinfunction "6_6") (pintype "input"))
    )
    (net (code "52") (name "Net-(IC1-I2P)") (class "Default")
      (node (ref "C4") (pin "1") (pinfunction "1_1") (pintype "unspecified"))
      (node (ref "IC1") (pin "5") (pinfunction "I2P_5") (pintype "unspecified"))
      (node (ref "R3") (pin "5") (pinfunction "5_5") (pintype "input"))
    )
    (net (code "53") (name "Net-(IC1-I3N)") (class "Default")
      (node (ref "C7") (pin "2") (pinfunction "2_2") (pintype "unspecified"))
      (node (ref "IC1") (pin "8") (pinfunction "I3N_8") (pintype "unspecified"))
      (node (ref "R5") (pin "2") (pinfunction "2_2") (pintype "input"))
    )
    (net (code "54") (name "Net-(IC1-I3P)") (class "Default")
      (node (ref "C6") (pin "1") (pinfunction "1_1") (pintype "unspecified"))
      (node (ref "IC1") (pin "7") (pinfunction "I3P_7") (pintype "unspecified"))
      (node (ref "R4") (pin "2") (pinfunction "2_2") (pintype "input"))
    )
    (net (code "55") (name "Net-(IC1-OSCI)") (class "Default")
      (node (ref "IC1") (pin "20") (pinfunction "OSCI_20") (pintype "unspecified"))
      (node (ref "X1") (pin "3") (pinfunction "OSC2_3") (pintype "unspecified"))
    )
    (net (code "56") (name "Net-(IC1-OSCO)") (class "Default")
      (node (ref "IC1") (pin "21") (pinfunction "OSCO_21") (pintype "unspecified"))
      (node (ref "X1") (pin "1") (pinfunction "OSC1_1") (pintype "unspecified"))
    )
    (net (code "57") (name "Net-(IC1-RESET#)") (class "Default")
      (node (ref "C1") (pin "2") (pinfunction "2_2") (pintype "unspecified"))
      (node (ref "IC1") (pin "41") (pinfunction "RESET#_41") (pintype "unspecified"))
      (node (ref "R1") (pin "1") (pinfunction "1_1") (pintype "unspecified"))
    )
    (net (code "58") (name "Net-(IC1-V1N)") (class "Default")
      (node (ref "C15") (pin "2") (pinfunction "2_2") (pintype "input"))
      (node (ref "IC1") (pin "14") (pinfunction "V1N_14") (pintype "unspecified"))
      (node (ref "IC1") (pin "16") (pinfunction "V2N_16") (pintype "unspecified"))
      (node (ref "IC1") (pin "18") (pinfunction "V3N_18") (pintype "unspecified"))
      (node (ref "R11") (pin "1") (pinfunction "1_1") (pintype "input"))
      (node (ref "R24") (pin "1") (pinfunction "1_1") (pintype "input"))
      (node (ref "R32") (pin "2") (pinfunction "2_2") (pintype "unspecified"))
    )
    (net (code "59") (name "Net-(IC1-V1P)") (class "Default")
      (node (ref "C14") (pin "2") (pinfunction "2_2") (pintype "input"))
      (node (ref "IC1") (pin "13") (pinfunction "V1P_13") (pintype "unspecified"))
      (node (ref "IC1") (pin "15") (pinfunction "V2P_15") (pintype "unspecified"))
      (node (ref "IC1") (pin "17") (pinfunction "V3P_17") (pintype "unspecified"))
      (node (ref "R11") (pin "4") (pinfunction "4_4") (pintype "input"))
      (node (ref "R24") (pin "4") (pinfunction "4_4") (pintype "input"))
      (node (ref "R28") (pin "2") (pinfunction "2_2") (pintype "unspecified"))
    )
    (net (code "60") (name "Net-(IC1-Vref)") (class "Default")
      (node (ref "C12") (pin "1") (pinfunction "1_1") (pintype "input"))
      (node (ref "C13") (pin "2") (pinfunction "2_2") (pintype "unspecified"))
      (node (ref "IC1") (pin "11") (pinfunction "Vref_11") (pintype "unspecified"))
    )
    (net (code "61") (name "Net-(IC1-ZX0)") (class "Default")
      (node (ref "IC1") (pin "22") (pinfunction "ZX0_22") (pintype "unspecified"))
      (node (ref "ZX0") (pin "1") (pinfunction "Pad_1") (pintype "unspecified"))
    )
    (net (code "62") (name "Net-(IC1-ZX1)") (class "Default")
      (node (ref "IC1") (pin "23") (pinfunction "ZX1_23") (pintype "unspecified"))
      (node (ref "ZX1") (pin "1") (pinfunction "Pad_1") (pintype "unspecified"))
    )
    (net (code "63") (name "Net-(IC1-ZX2)") (class "Default")
      (node (ref "IC1") (pin "24") (pinfunction "ZX2_24") (pintype "unspecified"))
      (node (ref "ZX2") (pin "1") (pinfunction "Pad_1") (pintype "unspecified"))
    )
    (net (code "64") (name "Net-(IC2-CF1)") (class "Default")
      (node (ref "IC2") (pin "25") (pinfunction "CF1_25") (pintype "unspecified"))
      (node (ref "R20") (pin "2") (pinfunction "2_2") (pintype "input"))
    )
    (net (code "65") (name "Net-(IC2-CF2)") (class "Default")
      (node (ref "CF2-2") (pin "1") (pinfunction "Pad_1") (pintype "unspecified"))
      (node (ref "IC2") (pin "26") (pinfunction "CF2_26") (pintype "unspecified"))
    )
    (net (code "66") (name "Net-(IC2-CF3)") (class "Default")
      (node (ref "CF3-2") (pin "1") (pinfunction "Pad_1") (pintype "unspecified"))
      (node (ref "IC2") (pin "27") (pinfunction "CF3_27") (pintype "unspecified"))
    )
    (net (code "67") (name "Net-(IC2-CF4)") (class "Default")
      (node (ref "CF4-2") (pin "1") (pinfunction "Pad_1") (pintype "unspecified"))
      (node (ref "IC2") (pin "28") (pinfunction "CF4_28") (pintype "unspecified"))
    )
    (net (code "68") (name "Net-(IC2-I1N)") (class "Default")
      (node (ref "C18") (pin "2") (pinfunction "2_2") (pintype "unspecified"))
      (node (ref "IC2") (pin "4") (pinfunction "I1N_4") (pintype "unspecified"))
      (node (ref "R14") (pin "8") (pinfunction "8_8") (pintype "input"))
    )
    (net (code "69") (name "Net-(IC2-I1P)") (class "Default")
      (node (ref "C17") (pin "1") (pinfunction "1_1") (pintype "unspecified"))
      (node (ref "IC2") (pin "3") (pinfunction "I1P_3") (pintype "unspecified"))
      (node (ref "R14") (pin "7") (pinfunction "7_7") (pintype "input"))
    )
    (net (code "70") (name "Net-(IC2-I2N)") (class "Default")
      (node (ref "C20") (pin "2") (pinfunction "2_2") (pintype "unspecified"))
      (node (ref "IC2") (pin "6") (pinfunction "I2N_6") (pintype "unspecified"))
      (node (ref "R14") (pin "6") (pinfunction "6_6") (pintype "input"))
    )
    (net (code "71") (name "Net-(IC2-I2P)") (class "Default")
      (node (ref "C19") (pin "1") (pinfunction "1_1") (pintype "unspecified"))
      (node (ref "IC2") (pin "5") (pinfunction "I2P_5") (pintype "unspecified"))
      (node (ref "R14") (pin "5") (pinfunction "5_5") (pintype "input"))
    )
    (net (code "72") (name "Net-(IC2-I3N)") (class "Default")
      (node (ref "C22") (pin "1") (pinfunction "1_1") (pintype "unspecified"))
      (node (ref "IC2") (pin "8") (pinfunction "I3N_8") (pintype "unspecified"))
      (node (ref "R16") (pin "2") (pinfunction "2_2") (pintype "input"))
    )
    (net (code "73") (name "Net-(IC2-I3P)") (class "Default")
      (node (ref "C21") (pin "2") (pinfunction "2_2") (pintype "unspecified"))
      (node (ref "IC2") (pin "7") (pinfunction "I3P_7") (pintype "unspecified"))
      (node (ref "R15") (pin "2") (pinfunction "2_2") (pintype "input"))
    )
    (net (code "74") (name "Net-(IC2-OSCI)") (class "Default")
      (node (ref "IC2") (pin "20") (pinfunction "OSCI_20") (pintype "unspecified"))
      (node (ref "X2") (pin "3") (pinfunction "OSC2_3") (pintype "unspecified"))
    )
    (net (code "75") (name "Net-(IC2-OSCO)") (class "Default")
      (node (ref "IC2") (pin "21") (pinfunction "OSCO_21") (pintype "unspecified"))
      (node (ref "X2") (pin "1") (pinfunction "OSC1_1") (pintype "unspecified"))
    )
    (net (code "76") (name "Net-(IC2-RESET#)") (class "Default")
      (node (ref "C16") (pin "2") (pinfunction "2_2") (pintype "unspecified"))
      (node (ref "IC2") (pin "41") (pinfunction "RESET#_41") (pintype "unspecified"))
      (node (ref "R12") (pin "1") (pinfunction "1_1") (pintype "unspecified"))
    )
    (net (code "77") (name "Net-(IC2-V1N)") (class "Default")
      (node (ref "C30") (pin "2") (pinfunction "2_2") (pintype "input"))
      (node (ref "IC2") (pin "14") (pinfunction "V1N_14") (pintype "unspecified"))
      (node (ref "IC2") (pin "16") (pinfunction "V2N_16") (pintype "unspecified"))
      (node (ref "IC2") (pin "18") (pinfunction "V3N_18") (pintype "unspecified"))
      (node (ref "R11") (pin "2") (pinfunction "2_2") (pintype "input"))
      (node (ref "R24") (pin "2") (pinfunction "2_2") (pintype "input"))
      (node (ref "R34") (pin "2") (pinfunction "2_2") (pintype "unspecified"))
    )
    (net (code "78") (name "Net-(IC2-V1P)") (class "Default")
      (node (ref "C29") (pin "2") (pinfunction "2_2") (pintype "input"))
      (node (ref "IC2") (pin "13") (pinfunction "V1P_13") (pintype "unspecified"))
      (node (ref "IC2") (pin "15") (pinfunction "V2P_15") (pintype "unspecified"))
      (node (ref "IC2") (pin "17") (pinfunction "V3P_17") (pintype "unspecified"))
      (node (ref "R11") (pin "3") (pinfunction "3_3") (pintype "input"))
      (node (ref "R24") (pin "3") (pinfunction "3_3") (pintype "input"))
      (node (ref "R26") (pin "2") (pinfunction "2_2") (pintype "unspecified"))
    )
    (net (code "79") (name "Net-(IC2-Vref)") (class "Default")
      (node (ref "C27") (pin "1") (pinfunction "1_1") (pintype "input"))
      (node (ref "C28") (pin "2") (pinfunction "2_2") (pintype "unspecified"))
      (node (ref "IC2") (pin "11") (pinfunction "Vref_11") (pintype "unspecified"))
    )
    (net (code "80") (name "Net-(IC2-ZX0)") (class "Default")
      (node (ref "IC2") (pin "22") (pinfunction "ZX0_22") (pintype "unspecified"))
      (node (ref "ZX3") (pin "1") (pinfunction "Pad_1") (pintype "unspecified"))
    )
    (net (code "81") (name "Net-(IC2-ZX1)") (class "Default")
      (node (ref "IC2") (pin "23") (pinfunction "ZX1_23") (pintype "unspecified"))
      (node (ref "ZX4") (pin "1") (pinfunction "Pad_1") (pintype "unspecified"))
    )
    (net (code "82") (name "Net-(IC2-ZX2)") (class "Default")
      (node (ref "IC2") (pin "24") (pinfunction "ZX2_24") (pintype "unspecified"))
      (node (ref "ZX5") (pin "1") (pinfunction "Pad_1") (pintype "unspecified"))
    )
    (net (code "83") (name "Net-(IC3-BOOT)") (class "Default")
      (node (ref "C31") (pin "2") (pinfunction "2_2") (pintype "unspecified"))
      (node (ref "IC3") (pin "1") (pinfunction "BOOT_1") (pintype "unspecified"))
    )
    (net (code "84") (name "Net-(IC3-FB)") (class "Default")
      (node (ref "C32") (pin "1") (pinfunction "1_1") (pintype "unspecified"))
      (node (ref "IC3") (pin "5") (pinfunction "FB_5") (pintype "unspecified"))
      (node (ref "R22") (pin "1") (pinfunction "1_1") (pintype "unspecified"))
      (node (ref "R23") (pin "2") (pinfunction "2_2") (pintype "unspecified"))
    )
    (net (code "85") (name "Net-(IC3-RT{slash}SYNC)") (class "Default")
      (node (ref "IC3") (pin "4") (pinfunction "RT/SYNC_4") (pintype "unspecified"))
      (node (ref "R21") (pin "2") (pinfunction "2_2") (pintype "unspecified"))
    )
    (net (code "86") (name "Net-(IC3-SS)") (class "Default")
      (node (ref "C35") (pin "2") (pinfunction "2_2") (pintype "input"))
      (node (ref "IC3") (pin "6") (pinfunction "SS_6") (pintype "unspecified"))
    )
    (net (code "87") (name "Net-(JP1-Pad1)") (class "Default")
      (node (ref "JP1") (pin "1") (pinfunction "1_1") (pintype "unspecified"))
      (node (ref "R7") (pin "1") (pinfunction "1_1") (pintype "unspecified"))
    )
    (net (code "88") (name "Net-(JP2-Pad1)") (class "Default")
      (node (ref "JP2") (pin "1") (pinfunction "1_1") (pintype "unspecified"))
      (node (ref "R8") (pin "1") (pinfunction "1_1") (pintype "unspecified"))
    )
    (net (code "89") (name "Net-(JP3-Pad1)") (class "Default")
      (node (ref "JP3") (pin "1") (pinfunction "1_1") (pintype "unspecified"))
      (node (ref "R6") (pin "1") (pinfunction "1_1") (pintype "unspecified"))
    )
    (net (code "90") (name "Net-(JP4-Pad1)") (class "Default")
      (node (ref "JP4") (pin "1") (pinfunction "1_1") (pintype "unspecified"))
      (node (ref "R18") (pin "1") (pinfunction "1_1") (pintype "unspecified"))
    )
    (net (code "91") (name "Net-(JP5-Pad1)") (class "Default")
      (node (ref "JP5") (pin "1") (pinfunction "1_1") (pintype "unspecified"))
      (node (ref "R19") (pin "1") (pinfunction "1_1") (pintype "unspecified"))
    )
    (net (code "92") (name "Net-(JP6-Pad1)") (class "Default")
      (node (ref "JP6") (pin "1") (pinfunction "1_1") (pintype "unspecified"))
      (node (ref "R17") (pin "1") (pinfunction "1_1") (pintype "unspecified"))
    )
    (net (code "93") (name "Net-(JP12-Pad2)") (class "Default")
      (node (ref "JP12") (pin "2") (pinfunction "2_2") (pintype "unspecified"))
      (node (ref "R28") (pin "1") (pinfunction "1_1") (pintype "unspecified"))
      (node (ref "VA2+") (pin "1") (pinfunction "Pad_1") (pintype "unspecified"))
    )
    (net (code "94") (name "Net-(JP13-Pad1)") (class "Default")
      (node (ref "JP13") (pin "1") (pinfunction "1_1") (pintype "unspecified"))
      (node (ref "R32") (pin "1") (pinfunction "1_1") (pintype "unspecified"))
      (node (ref "VA2-") (pin "1") (pinfunction "Pad_1") (pintype "unspecified"))
    )
    (net (code "95") (name "Net-(PWR-A)") (class "Default")
      (node (ref "PWR") (pin "1") (pinfunction "A_1") (pintype "unspecified"))
      (node (ref "R10") (pin "1") (pinfunction "1_1") (pintype "unspecified"))
    )
    (net (code "96") (name "VCC") (class "Default")
      (node (ref "3V3") (pin "1") (pinfunction "Pad_1") (pintype "unspecified"))
      (node (ref "C10") (pin "2") (pinfunction "2_2") (pintype "unspecified"))
      (node (ref "C11") (pin "2") (pinfunction "2_2") (pintype "unspecified"))
      (node (ref "C25") (pin "2") (pinfunction "2_2") (pintype "unspecified"))
      (node (ref "C26") (pin "2") (pinfunction "2_2") (pintype "unspecified"))
      (node (ref "C32") (pin "2") (pinfunction "2_2") (pintype "unspecified"))
      (node (ref "C36") (pin "2") (pinfunction "2_2") (pintype "unspecified"))
      (node (ref "ESP32") (pin "1") (pinfunction "3V3_1") (pintype "bidirectional"))
      (node (ref "IC1") (pin "1") (pinfunction "AVDD_1") (pintype "unspecified"))
      (node (ref "IC1") (pin "33") (pinfunction "PM0_33") (pintype "unspecified"))
      (node (ref "IC1") (pin "34") (pinfunction "PM1_34") (pintype "unspecified"))
      (node (ref "IC1") (pin "48") (pinfunction "DVDD_48") (pintype "unspecified"))
      (node (ref "IC2") (pin "1") (pinfunction "AVDD_1") (pintype "unspecified"))
      (node (ref "IC2") (pin "33") (pinfunction "PM0_33") (pintype "unspecified"))
      (node (ref "IC2") (pin "34") (pinfunction "PM1_34") (pintype "unspecified"))
      (node (ref "IC2") (pin "48") (pinfunction "DVDD_48") (pintype "unspecified"))
      (node (ref "L1") (pin "2") (pinfunction "2_2") (pintype "unspecified"))
      (node (ref "R1") (pin "2") (pinfunction "2_2") (pintype "unspecified"))
      (node (ref "R10") (pin "2") (pinfunction "2_2") (pintype "unspecified"))
      (node (ref "R12") (pin "2") (pinfunction "2_2") (pintype "unspecified"))
      (node (ref "R13") (pin "2") (pinfunction "2_2") (pintype "unspecified"))
      (node (ref "R2") (pin "5") (pinfunction "5_5") (pintype "input"))
      (node (ref "R2") (pin "6") (pinfunction "6_6") (pintype "input"))
      (node (ref "R2") (pin "7") (pinfunction "7_7") (pintype "input"))
      (node (ref "R2") (pin "8") (pinfunction "8_8") (pintype "input"))
      (node (ref "R22") (pin "2") (pinfunction "2_2") (pintype "unspecified"))
      (node (ref "R24") (pin "5") (pinfunction "5_5") (pintype "input"))
      (node (ref "R24") (pin "6") (pinfunction "6_6") (pintype "input"))
      (node (ref "R24") (pin "7") (pinfunction "7_7") (pintype "input"))
      (node (ref "R24") (pin "8") (pinfunction "8_8") (pintype "input"))
      (node (ref "R27") (pin "2") (pinfunction "2_2") (pintype "unspecified"))
    )
    (net (code "97") (name "unconnected-(AC-Pad3)") (class "Default")
      (node (ref "AC") (pin "3") (pinfunction "3_3") (pintype "unspecified"))
    )
    (net (code "98") (name "unconnected-(CT1-Pad2)") (class "Default")
      (node (ref "CT1") (pin "2") (pinfunction "2_2") (pintype "unspecified+no_connect"))
    )
    (net (code "99") (name "unconnected-(CT1-Pad3)") (class "Default")
      (node (ref "CT1") (pin "3") (pinfunction "3_3") (pintype "unspecified+no_connect"))
    )
    (net (code "100") (name "unconnected-(CT2-Pad2)") (class "Default")
      (node (ref "CT2") (pin "2") (pinfunction "2_2") (pintype "unspecified+no_connect"))
    )
    (net (code "101") (name "unconnected-(CT2-Pad3)") (class "Default")
      (node (ref "CT2") (pin "3") (pinfunction "3_3") (pintype "unspecified+no_connect"))
    )
    (net (code "102") (name "unconnected-(CT3-Pad2)") (class "Default")
      (node (ref "CT3") (pin "2") (pinfunction "2_2") (pintype "unspecified+no_connect"))
    )
    (net (code "103") (name "unconnected-(CT3-Pad3)") (class "Default")
      (node (ref "CT3") (pin "3") (pinfunction "3_3") (pintype "unspecified+no_connect"))
    )
    (net (code "104") (name "unconnected-(CT4-Pad2)") (class "Default")
      (node (ref "CT4") (pin "2") (pinfunction "2_2") (pintype "unspecified+no_connect"))
    )
    (net (code "105") (name "unconnected-(CT4-Pad3)") (class "Default")
      (node (ref "CT4") (pin "3") (pinfunction "3_3") (pintype "unspecified+no_connect"))
    )
    (net (code "106") (name "unconnected-(CT5-Pad2)") (class "Default")
      (node (ref "CT5") (pin "2") (pinfunction "2_2") (pintype "unspecified+no_connect"))
    )
    (net (code "107") (name "unconnected-(CT5-Pad3)") (class "Default")
      (node (ref "CT5") (pin "3") (pinfunction "3_3") (pintype "unspecified+no_connect"))
    )
    (net (code "108") (name "unconnected-(CT6-Pad2)") (class "Default")
      (node (ref "CT6") (pin "2") (pinfunction "2_2") (pintype "unspecified+no_connect"))
    )
    (net (code "109") (name "unconnected-(CT6-Pad3)") (class "Default")
      (node (ref "CT6") (pin "3") (pinfunction "3_3") (pintype "unspecified+no_connect"))
    )
    (net (code "110") (name "unconnected-(ESP32-CLK-Pad38)") (class "Default")
      (node (ref "ESP32") (pin "38") (pinfunction "CLK_38") (pintype "bidirectional+no_connect"))
    )
    (net (code "111") (name "unconnected-(ESP32-CMD-Pad18)") (class "Default")
      (node (ref "ESP32") (pin "18") (pinfunction "CMD_18") (pintype "bidirectional+no_connect"))
    )
    (net (code "112") (name "unconnected-(ESP32-EN-Pad2)") (class "Default")
      (node (ref "ESP32") (pin "2") (pinfunction "EN_2") (pintype "bidirectional+no_connect"))
    )
    (net (code "113") (name "unconnected-(ESP32-EXT_5V-Pad19)") (class "Default")
      (node (ref "ESP32") (pin "19") (pinfunction "EXT_5V_19") (pintype "bidirectional+no_connect"))
    )
    (net (code "114") (name "unconnected-(ESP32-RXD0-Pad24)") (class "Default")
      (node (ref "ESP32") (pin "24") (pinfunction "RXD0_24") (pintype "bidirectional+no_connect"))
    )
    (net (code "115") (name "unconnected-(ESP32-SD0-Pad37)") (class "Default")
      (node (ref "ESP32") (pin "37") (pinfunction "SD0_37") (pintype "bidirectional+no_connect"))
    )
    (net (code "116") (name "unconnected-(ESP32-SD1-Pad36)") (class "Default")
      (node (ref "ESP32") (pin "36") (pinfunction "SD1_36") (pintype "bidirectional+no_connect"))
    )
    (net (code "117") (name "unconnected-(ESP32-SD2-Pad16)") (class "Default")
      (node (ref "ESP32") (pin "16") (pinfunction "SD2_16") (pintype "bidirectional+no_connect"))
    )
    (net (code "118") (name "unconnected-(ESP32-SD3-Pad17)") (class "Default")
      (node (ref "ESP32") (pin "17") (pinfunction "SD3_17") (pintype "bidirectional+no_connect"))
    )
    (net (code "119") (name "unconnected-(ESP32-SENSOR_VN-Pad4)") (class "Default")
      (node (ref "ESP32") (pin "4") (pinfunction "SENSOR_VN_4") (pintype "bidirectional+no_connect"))
    )
    (net (code "120") (name "unconnected-(ESP32-TXD0-Pad23)") (class "Default")
      (node (ref "ESP32") (pin "23") (pinfunction "TXD0_23") (pintype "bidirectional+no_connect"))
    )
    (net (code "121") (name "unconnected-(IC1-IC-Pad9)") (class "Default")
      (node (ref "IC1") (pin "9") (pinfunction "IC_9") (pintype "unspecified+no_connect"))
    )
    (net (code "122") (name "unconnected-(IC1-IC-Pad10)") (class "Default")
      (node (ref "IC1") (pin "10") (pinfunction "IC_10") (pintype "unspecified+no_connect"))
    )
    (net (code "123") (name "unconnected-(IC1-NC-Pad35)") (class "Default")
      (node (ref "IC1") (pin "35") (pinfunction "NC_35") (pintype "unspecified+no_connect"))
    )
    (net (code "124") (name "unconnected-(IC1-NC-Pad45)") (class "Default")
      (node (ref "IC1") (pin "45") (pinfunction "NC_45") (pintype "unspecified+no_connect"))
    )
    (net (code "125") (name "unconnected-(IC1-NC-Pad46)") (class "Default")
      (node (ref "IC1") (pin "46") (pinfunction "NC_46") (pintype "unspecified+no_connect"))
    )
    (net (code "126") (name "unconnected-(IC2-IC-Pad9)") (class "Default")
      (node (ref "IC2") (pin "9") (pinfunction "IC_9") (pintype "unspecified+no_connect"))
    )
    (net (code "127") (name "unconnected-(IC2-IC-Pad10)") (class "Default")
      (node (ref "IC2") (pin "10") (pinfunction "IC_10") (pintype "unspecified+no_connect"))
    )
    (net (code "128") (name "unconnected-(IC2-NC-Pad35)") (class "Default")
      (node (ref "IC2") (pin "35") (pinfunction "NC_35") (pintype "unspecified+no_connect"))
    )
    (net (code "129") (name "unconnected-(IC2-NC-Pad45)") (class "Default")
      (node (ref "IC2") (pin "45") (pinfunction "NC_45") (pintype "unspecified+no_connect"))
    )
    (net (code "130") (name "unconnected-(IC2-NC-Pad46)") (class "Default")
      (node (ref "IC2") (pin "46") (pinfunction "NC_46") (pintype "unspecified+no_connect"))
    )
  )
)
